# Sheet1.net
KiCad netlist of a schematic drawn in Altium Designer
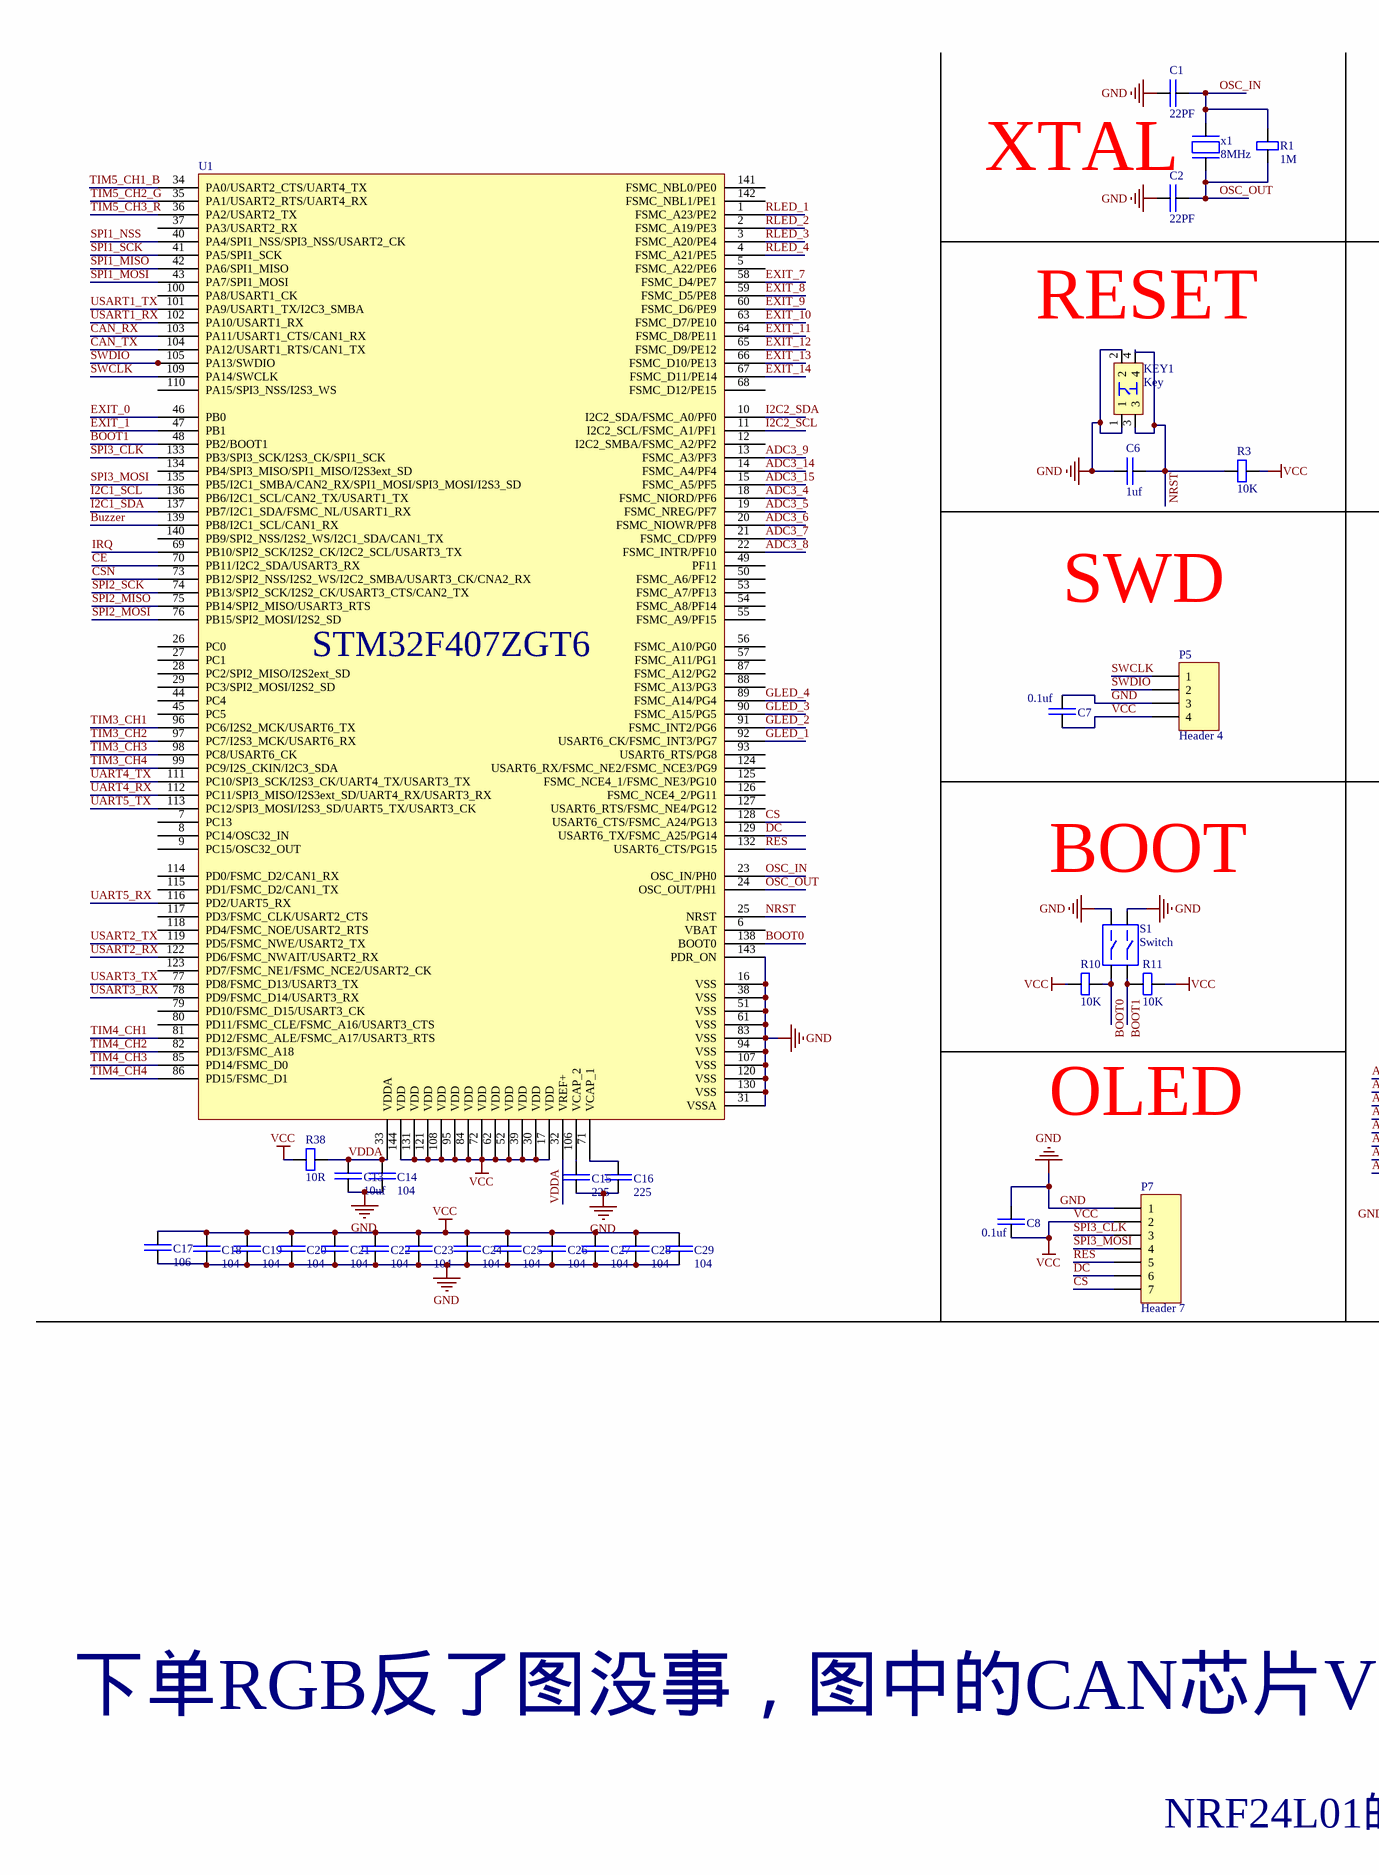
[diagram p0: Sheet1.SchDoc, left]
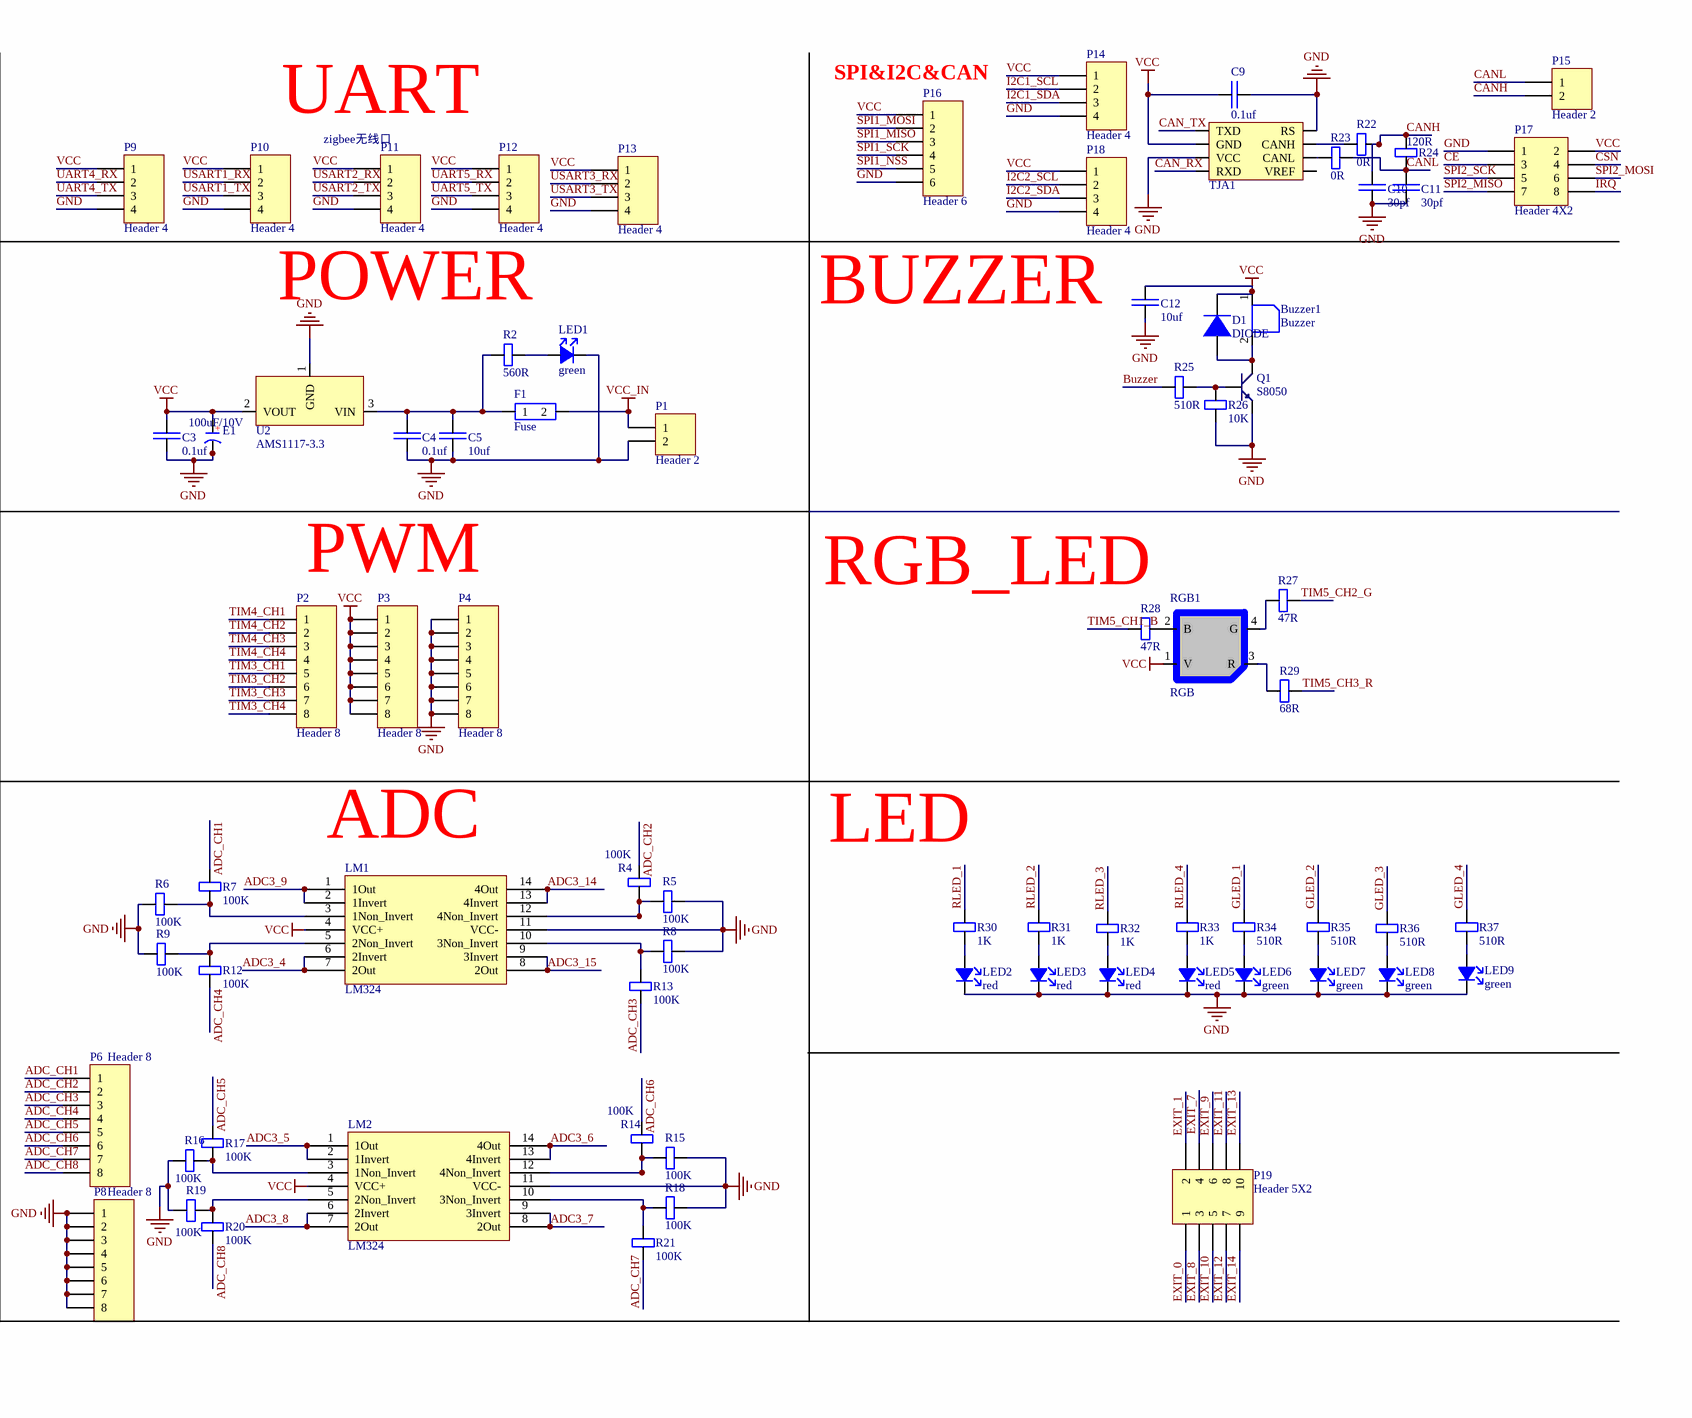
[diagram p1: Sheet1.SchDoc, right]

(export (version "E")
  (design (tool "Eeschema 10.0.6"))
  (components
    (comp (ref "Buzzer1") (value "Buzzer") (footprint "BUZZER") (libsource (lib "Schlib1") (part "Buzzer")))
    (comp (ref "C1") (value "22PF") (footprint "0402") (libsource (lib "Schlib1") (part "C")))
    (comp (ref "C2") (value "22PF") (footprint "0402") (libsource (lib "Schlib1") (part "C")))
    (comp (ref "C3") (value "0.1uf") (footprint "0402") (libsource (lib "Schlib1") (part "C")))
    (comp (ref "C4") (value "0.1uf") (footprint "0402") (libsource (lib "Schlib1") (part "C")))
    (comp (ref "C5") (value "10uf") (footprint "0402") (libsource (lib "Schlib1") (part "C")))
    (comp (ref "C6") (value "1uf") (footprint "0402") (libsource (lib "Schlib1") (part "C")))
    (comp (ref "C7") (value "0.1uf") (footprint "0402") (libsource (lib "Schlib1") (part "C")))
    (comp (ref "C8") (value "0.1uf") (footprint "0402") (libsource (lib "Schlib1") (part "C")))
    (comp (ref "C9") (value "0.1uf") (footprint "0402") (libsource (lib "Schlib1") (part "C")))
    (comp (ref "C10") (value "30pf") (footprint "0402") (libsource (lib "Schlib1") (part "C")))
    (comp (ref "C11") (value "30pf") (footprint "0402") (libsource (lib "Schlib1") (part "C")))
    (comp (ref "C12") (value "10uf") (footprint "0402") (libsource (lib "Schlib1") (part "C")))
    (comp (ref "C13") (value "10uf") (footprint "0402") (libsource (lib "Schlib1") (part "C")))
    (comp (ref "C14") (value "104") (footprint "0402") (libsource (lib "Schlib1") (part "C")))
    (comp (ref "C15") (value "225") (footprint "0402") (libsource (lib "Schlib1") (part "C")))
    (comp (ref "C16") (value "225") (footprint "0402") (libsource (lib "Schlib1") (part "C")))
    (comp (ref "C17") (value "106") (footprint "0402") (libsource (lib "Schlib1") (part "C")))
    (comp (ref "C18") (value "104") (footprint "0402") (libsource (lib "Schlib1") (part "C")))
    (comp (ref "C19") (value "104") (footprint "0402") (libsource (lib "Schlib1") (part "C")))
    (comp (ref "C20") (value "104") (footprint "0402") (libsource (lib "Schlib1") (part "C")))
    (comp (ref "C21") (value "104") (footprint "0402") (libsource (lib "Schlib1") (part "C")))
    (comp (ref "C22") (value "104") (footprint "0402") (libsource (lib "Schlib1") (part "C")))
    (comp (ref "C23") (value "104") (footprint "0402") (libsource (lib "Schlib1") (part "C")))
    (comp (ref "C24") (value "104") (footprint "0402") (libsource (lib "Schlib1") (part "C")))
    (comp (ref "C25") (value "104") (footprint "0402") (libsource (lib "Schlib1") (part "C")))
    (comp (ref "C26") (value "104") (footprint "0402") (libsource (lib "Schlib1") (part "C")))
    (comp (ref "C27") (value "104") (footprint "0402") (libsource (lib "Schlib1") (part "C")))
    (comp (ref "C28") (value "104") (footprint "0402") (libsource (lib "Schlib1") (part "C")))
    (comp (ref "C29") (value "104") (footprint "0402") (libsource (lib "Schlib1") (part "C")))
    (comp (ref "D1") (value "DIODE") (footprint "DIODE") (libsource (lib "Schlib1") (part "DIODE")))
    (comp (ref "E1")
      (value "100uF/10V")
      (footprint "3528")
      (description "钽电容")
      (fields (field (name "版权归属") "源创客"))
      (libsource (lib "电阻-电容-电感") (part "C-CM"))
    )
    (comp (ref "F1") (value "Fuse") (footprint "0805") (libsource (lib "Schlib1") (part "Fuse")))
    (comp (ref "KEY1") (value "Key") (footprint "6*6*5轻触开关") (libsource (lib "Schlib1") (part "Key")))
    (comp (ref "LED1") (value "green") (footprint "0603") (libsource (lib "Schlib1") (part "LED")))
    (comp (ref "LED2") (value "red") (footprint "0603") (libsource (lib "Schlib1") (part "LED")))
    (comp (ref "LED3") (value "red") (footprint "0603") (libsource (lib "Schlib1") (part "LED")))
    (comp (ref "LED4") (value "red") (footprint "0603") (libsource (lib "Schlib1") (part "LED")))
    (comp (ref "LED5") (value "red") (footprint "0603") (libsource (lib "Schlib1") (part "LED")))
    (comp (ref "LED6") (value "green") (footprint "0603") (libsource (lib "Schlib1") (part "LED")))
    (comp (ref "LED7") (value "green") (footprint "0603") (libsource (lib "Schlib1") (part "LED")))
    (comp (ref "LED8") (value "green") (footprint "0603") (libsource (lib "Schlib1") (part "LED")))
    (comp (ref "LED9") (value "green") (footprint "0603") (libsource (lib "Schlib1") (part "LED")))
    (comp (ref "LM1") (value "LM324") (footprint "LM324") (libsource (lib "Schlib1") (part "LM324")))
    (comp (ref "LM2") (value "LM324") (footprint "LM324") (libsource (lib "Schlib1") (part "LM324")))
    (comp (ref "P1")
      (value "Header 2")
      (footprint "XT30-PW-M")
      (description "Header, 2-Pin")
      (fields (field (name "PUBLISHER") "Altium Limited"))
      (libsource (lib "Miscellaneous Connectors") (part "Header 2"))
    )
    (comp (ref "P2")
      (value "Header 8")
      (footprint "HDR1X8")
      (description "Header, 8-Pin")
      (fields (field (name "PUBLISHER") "Altium Limited"))
      (libsource (lib "Miscellaneous Connectors") (part "Header 8"))
    )
    (comp (ref "P3")
      (value "Header 8")
      (footprint "HDR1X8")
      (description "Header, 8-Pin")
      (fields (field (name "PUBLISHER") "Altium Limited"))
      (libsource (lib "Miscellaneous Connectors") (part "Header 8"))
    )
    (comp (ref "P4")
      (value "Header 8")
      (footprint "HDR1X8")
      (description "Header, 8-Pin")
      (fields (field (name "PUBLISHER") "Altium Limited"))
      (libsource (lib "Miscellaneous Connectors") (part "Header 8"))
    )
    (comp (ref "P5")
      (value "Header 4")
      (footprint "GH1.25_4P")
      (description "Header, 4-Pin")
      (fields (field (name "PUBLISHER") "Altium Limited"))
      (libsource (lib "Miscellaneous Connectors") (part "Header 4"))
    )
    (comp (ref "P6")
      (value "Header 8")
      (footprint "HDR1X8")
      (description "Header, 8-Pin")
      (fields (field (name "PUBLISHER") "Altium Limited"))
      (libsource (lib "Miscellaneous Connectors") (part "Header 8"))
    )
    (comp (ref "P7")
      (value "Header 7")
      (footprint "HDR1X7")
      (description "Header, 7-Pin")
      (fields (field (name "PUBLISHER") "Altium Limited"))
      (libsource (lib "Miscellaneous Connectors") (part "Header 7"))
    )
    (comp (ref "P8")
      (value "Header 8")
      (footprint "HDR1X8")
      (description "Header, 8-Pin")
      (fields (field (name "PUBLISHER") "Altium Limited"))
      (libsource (lib "Miscellaneous Connectors") (part "Header 8"))
    )
    (comp (ref "P9")
      (value "Header 4")
      (footprint "GH1.25_4P")
      (description "Header, 4-Pin")
      (fields (field (name "PUBLISHER") "Altium Limited"))
      (libsource (lib "Miscellaneous Connectors") (part "Header 4"))
    )
    (comp (ref "P10")
      (value "Header 4")
      (footprint "GH1.25_4P")
      (description "Header, 4-Pin")
      (fields (field (name "PUBLISHER") "Altium Limited"))
      (libsource (lib "Miscellaneous Connectors") (part "Header 4"))
    )
    (comp (ref "P11")
      (value "Header 4")
      (footprint "GH1.25_4P")
      (description "Header, 4-Pin")
      (fields (field (name "PUBLISHER") "Altium Limited"))
      (libsource (lib "Miscellaneous Connectors") (part "Header 4"))
    )
    (comp (ref "P12")
      (value "Header 4")
      (footprint "GH1.25_4P")
      (description "Header, 4-Pin")
      (fields (field (name "PUBLISHER") "Altium Limited"))
      (libsource (lib "Miscellaneous Connectors") (part "Header 4"))
    )
    (comp (ref "P13")
      (value "Header 4")
      (footprint "GH1.25_4P")
      (description "Header, 4-Pin")
      (fields (field (name "PUBLISHER") "Altium Limited"))
      (libsource (lib "Miscellaneous Connectors") (part "Header 4"))
    )
    (comp (ref "P14")
      (value "Header 4")
      (footprint "GH1.25_4P")
      (description "Header, 4-Pin")
      (fields (field (name "PUBLISHER") "Altium Limited"))
      (libsource (lib "Miscellaneous Connectors") (part "Header 4"))
    )
    (comp (ref "P15")
      (value "Header 2")
      (footprint "GH1.25_2P")
      (description "Header, 2-Pin")
      (fields (field (name "PUBLISHER") "Altium Limited"))
      (libsource (lib "Miscellaneous Connectors") (part "Header 2"))
    )
    (comp (ref "P16")
      (value "Header 6")
      (footprint "HDR1X6")
      (description "Header, 6-Pin")
      (fields (field (name "PUBLISHER") "Altium Limited"))
      (libsource (lib "Miscellaneous Connectors") (part "Header 6"))
    )
    (comp (ref "P17")
      (value "Header 4X2")
      (footprint "HDR2X4")
      (description "Header, 4-Pin, Dual row")
      (fields (field (name "PUBLISHER") "Altium Limited"))
      (libsource (lib "Miscellaneous Connectors") (part "Header 4X2"))
    )
    (comp (ref "P18")
      (value "Header 4")
      (footprint "GH1.25_4P")
      (description "Header, 4-Pin")
      (fields (field (name "PUBLISHER") "Altium Limited"))
      (libsource (lib "Miscellaneous Connectors") (part "Header 4"))
    )
    (comp (ref "P19")
      (value "Header 5X2")
      (footprint "HDR2X5")
      (description "Header, 5-Pin, Dual row")
      (fields (field (name "PUBLISHER") "Altium Limited"))
      (libsource (lib "Miscellaneous Connectors") (part "Header 5X2"))
    )
    (comp (ref "Q1")
      (value "S8050")
      (footprint "SOT-23R")
      (description "8050/BCW846/BCW847")
      (libsource (lib "REMOTOR V1.6") (part "NPN"))
    )
    (comp (ref "R1") (value "1M") (footprint "0402") (libsource (lib "Schlib1") (part "R")))
    (comp (ref "R2") (value "560R") (footprint "0402") (libsource (lib "Schlib1") (part "R")))
    (comp (ref "R3") (value "10K") (footprint "0402") (libsource (lib "Schlib1") (part "R")))
    (comp (ref "R4") (value "100K") (footprint "0402") (libsource (lib "Schlib1") (part "R")))
    (comp (ref "R5") (value "100K") (footprint "0402") (libsource (lib "Schlib1") (part "R")))
    (comp (ref "R6") (value "100K") (footprint "0402") (libsource (lib "Schlib1") (part "R")))
    (comp (ref "R7") (value "100K") (footprint "0402") (libsource (lib "Schlib1") (part "R")))
    (comp (ref "R8") (value "100K") (footprint "0402") (libsource (lib "Schlib1") (part "R")))
    (comp (ref "R9") (value "100K") (footprint "0402") (libsource (lib "Schlib1") (part "R")))
    (comp (ref "R10") (value "10K") (footprint "0402") (libsource (lib "Schlib1") (part "R")))
    (comp (ref "R11") (value "10K") (footprint "0402") (libsource (lib "Schlib1") (part "R")))
    (comp (ref "R12") (value "100K") (footprint "0402") (libsource (lib "Schlib1") (part "R")))
    (comp (ref "R13") (value "100K") (footprint "0402") (libsource (lib "Schlib1") (part "R")))
    (comp (ref "R14") (value "100K") (footprint "0402") (libsource (lib "Schlib1") (part "R")))
    (comp (ref "R15") (value "100K") (footprint "0402") (libsource (lib "Schlib1") (part "R")))
    (comp (ref "R16") (value "100K") (footprint "0402") (libsource (lib "Schlib1") (part "R")))
    (comp (ref "R17") (value "100K") (footprint "0402") (libsource (lib "Schlib1") (part "R")))
    (comp (ref "R18") (value "100K") (footprint "0402") (libsource (lib "Schlib1") (part "R")))
    (comp (ref "R19") (value "100K") (footprint "0402") (libsource (lib "Schlib1") (part "R")))
    (comp (ref "R20") (value "100K") (footprint "0402") (libsource (lib "Schlib1") (part "R")))
    (comp (ref "R21") (value "100K") (footprint "0402") (libsource (lib "Schlib1") (part "R")))
    (comp (ref "R22") (value "0R") (footprint "0402") (libsource (lib "Schlib1") (part "R")))
    (comp (ref "R23") (value "0R") (footprint "0402") (libsource (lib "Schlib1") (part "R")))
    (comp (ref "R24") (value "120R") (footprint "0402") (libsource (lib "Schlib1") (part "R")))
    (comp (ref "R25") (value "510R") (footprint "0402") (libsource (lib "Schlib1") (part "R")))
    (comp (ref "R26") (value "10K") (footprint "0402") (libsource (lib "Schlib1") (part "R")))
    (comp (ref "R27") (value "47R") (footprint "0402") (libsource (lib "Schlib1") (part "R")))
    (comp (ref "R28") (value "47R") (footprint "0402") (libsource (lib "Schlib1") (part "R")))
    (comp (ref "R29") (value "68R") (footprint "0402") (libsource (lib "Schlib1") (part "R")))
    (comp (ref "R30") (value "1K") (footprint "0402") (libsource (lib "Schlib1") (part "R")))
    (comp (ref "R31") (value "1K") (footprint "0402") (libsource (lib "Schlib1") (part "R")))
    (comp (ref "R32") (value "1K") (footprint "0402") (libsource (lib "Schlib1") (part "R")))
    (comp (ref "R33") (value "1K") (footprint "0402") (libsource (lib "Schlib1") (part "R")))
    (comp (ref "R34") (value "510R") (footprint "0402") (libsource (lib "Schlib1") (part "R")))
    (comp (ref "R35") (value "510R") (footprint "0402") (libsource (lib "Schlib1") (part "R")))
    (comp (ref "R36") (value "510R") (footprint "0402") (libsource (lib "Schlib1") (part "R")))
    (comp (ref "R37") (value "510R") (footprint "0402") (libsource (lib "Schlib1") (part "R")))
    (comp (ref "R38") (value "10R") (footprint "0402") (libsource (lib "Schlib1") (part "R")))
    (comp (ref "RGB1") (value "RGB") (footprint "RGB_LED") (libsource (lib "Schlib1") (part "RGB")))
    (comp (ref "S1") (value "Switch") (footprint "SWITCH_2P") (libsource (lib "Schlib1") (part "Switch")))
    (comp (ref "TJA1") (value "TJA1050") (footprint "TJA1050") (libsource (lib "Schlib1") (part "TJA1050")))
    (comp (ref "U1")
      (value "STM32F407ZGT6")
      (footprint "STM32F103ZETx")
      (libsource (lib "Schlib1") (part "STM32F407ZGT6"))
    )
    (comp (ref "U2")
      (value "AMS1117-3.3")
      (footprint "ASM1117")
      (libsource (lib "Schlib1") (part "AMS1117-3.3"))
    )
    (comp (ref "x1") (value "8MHz") (footprint "8M晶振") (libsource (lib "Schlib1") (part "XTAL_8MHz")))
  )
  (nets
    (net (code "1") (name "/ADC3_4") (class "Default")
      (node (ref "LM1") (pin "6") (pinfunction "2Invert_6") (pintype "passive"))
      (node (ref "LM1") (pin "7") (pinfunction "2Out_7") (pintype "passive"))
      (node (ref "U1") (pin "18") (pinfunction "FSMC_NIORD/PF6_18") (pintype "passive"))
    )
    (net (code "2") (name "/ADC3_5") (class "Default")
      (node (ref "LM2") (pin "1") (pinfunction "1Out_1") (pintype "passive"))
      (node (ref "LM2") (pin "2") (pinfunction "1Invert_2") (pintype "passive"))
      (node (ref "U1") (pin "19") (pinfunction "FSMC_NREG/PF7_19") (pintype "passive"))
    )
    (net (code "3") (name "/ADC3_6") (class "Default")
      (node (ref "LM2") (pin "13") (pinfunction "4Invert_13") (pintype "passive"))
      (node (ref "LM2") (pin "14") (pinfunction "4Out_14") (pintype "passive"))
      (node (ref "U1") (pin "20") (pinfunction "FSMC_NIOWR/PF8_20") (pintype "passive"))
    )
    (net (code "4") (name "/ADC3_7") (class "Default")
      (node (ref "LM2") (pin "8") (pinfunction "2Out_8") (pintype "passive"))
      (node (ref "LM2") (pin "9") (pinfunction "3Invert_9") (pintype "passive"))
      (node (ref "U1") (pin "21") (pinfunction "FSMC_CD/PF9_21") (pintype "passive"))
    )
    (net (code "5") (name "/ADC3_8") (class "Default")
      (node (ref "LM2") (pin "6") (pinfunction "2Invert_6") (pintype "passive"))
      (node (ref "LM2") (pin "7") (pinfunction "2Out_7") (pintype "passive"))
      (node (ref "U1") (pin "22") (pinfunction "FSMC_INTR/PF10_22") (pintype "passive"))
    )
    (net (code "6") (name "/ADC3_9") (class "Default")
      (node (ref "LM1") (pin "1") (pinfunction "1Out_1") (pintype "passive"))
      (node (ref "LM1") (pin "2") (pinfunction "1Invert_2") (pintype "passive"))
      (node (ref "U1") (pin "13") (pinfunction "FSMC_A3/PF3_13") (pintype "passive"))
    )
    (net (code "7") (name "/ADC3_14") (class "Default")
      (node (ref "LM1") (pin "13") (pinfunction "4Invert_13") (pintype "passive"))
      (node (ref "LM1") (pin "14") (pinfunction "4Out_14") (pintype "passive"))
      (node (ref "U1") (pin "14") (pinfunction "FSMC_A4/PF4_14") (pintype "passive"))
    )
    (net (code "8") (name "/ADC3_15") (class "Default")
      (node (ref "LM1") (pin "8") (pinfunction "2Out_8") (pintype "passive"))
      (node (ref "LM1") (pin "9") (pinfunction "3Invert_9") (pintype "passive"))
      (node (ref "U1") (pin "15") (pinfunction "FSMC_A5/PF5_15") (pintype "passive"))
    )
    (net (code "9") (name "/ADC_CH1") (class "Default")
      (node (ref "P6") (pin "1") (pinfunction "1_1") (pintype "passive"))
      (node (ref "R7") (pin "2") (pinfunction "2_2") (pintype "passive"))
    )
    (net (code "10") (name "/ADC_CH2") (class "Default")
      (node (ref "P6") (pin "2") (pinfunction "2_2") (pintype "passive"))
      (node (ref "R4") (pin "1") (pinfunction "1_1") (pintype "passive"))
    )
    (net (code "11") (name "/ADC_CH3") (class "Default")
      (node (ref "P6") (pin "3") (pinfunction "3_3") (pintype "passive"))
      (node (ref "R13") (pin "2") (pinfunction "2_2") (pintype "passive"))
    )
    (net (code "12") (name "/ADC_CH4") (class "Default")
      (node (ref "P6") (pin "4") (pinfunction "4_4") (pintype "passive"))
      (node (ref "R12") (pin "2") (pinfunction "2_2") (pintype "passive"))
    )
    (net (code "13") (name "/ADC_CH5") (class "Default")
      (node (ref "P6") (pin "5") (pinfunction "5_5") (pintype "passive"))
      (node (ref "R17") (pin "2") (pinfunction "2_2") (pintype "passive"))
    )
    (net (code "14") (name "/ADC_CH6") (class "Default")
      (node (ref "P6") (pin "6") (pinfunction "6_6") (pintype "passive"))
      (node (ref "R14") (pin "1") (pinfunction "1_1") (pintype "passive"))
    )
    (net (code "15") (name "/ADC_CH7") (class "Default")
      (node (ref "P6") (pin "7") (pinfunction "7_7") (pintype "passive"))
      (node (ref "R21") (pin "2") (pinfunction "2_2") (pintype "passive"))
    )
    (net (code "16") (name "/ADC_CH8") (class "Default")
      (node (ref "P6") (pin "8") (pinfunction "8_8") (pintype "passive"))
      (node (ref "R20") (pin "2") (pinfunction "2_2") (pintype "passive"))
    )
    (net (code "17") (name "/BOOT0") (class "Default")
      (node (ref "R10") (pin "1") (pinfunction "1_1") (pintype "passive"))
      (node (ref "S1") (pin "2") (pinfunction "156_2") (pintype "passive"))
      (node (ref "U1") (pin "138") (pinfunction "BOOT0_138") (pintype "passive"))
    )
    (net (code "18") (name "/BOOT1") (class "Default")
      (node (ref "R11") (pin "2") (pinfunction "2_2") (pintype "passive"))
      (node (ref "S1") (pin "4") (pinfunction "157_4") (pintype "passive"))
      (node (ref "U1") (pin "48") (pinfunction "PB2/BOOT1_48") (pintype "passive"))
    )
    (net (code "19") (name "/Buzzer") (class "Default")
      (node (ref "R25") (pin "1") (pinfunction "1_1") (pintype "passive"))
      (node (ref "U1") (pin "139") (pinfunction "PB8/I2C1_SCL/CAN1_RX_139") (pintype "passive"))
    )
    (net (code "20") (name "/CANH") (class "Default")
      (node (ref "C10") (pin "2") (pinfunction "2_2") (pintype "passive"))
      (node (ref "P15") (pin "2") (pinfunction "2_2") (pintype "passive"))
      (node (ref "R22") (pin "2") (pinfunction "2_2") (pintype "passive"))
      (node (ref "R24") (pin "2") (pinfunction "2_2") (pintype "passive"))
    )
    (net (code "21") (name "/CANL") (class "Default")
      (node (ref "C11") (pin "2") (pinfunction "2_2") (pintype "passive"))
      (node (ref "P15") (pin "1") (pinfunction "1_1") (pintype "passive"))
      (node (ref "R23") (pin "2") (pinfunction "2_2") (pintype "passive"))
      (node (ref "R24") (pin "1") (pinfunction "1_1") (pintype "passive"))
    )
    (net (code "22") (name "/CAN_RX") (class "Default")
      (node (ref "TJA1") (pin "4") (pinfunction "RXD_4") (pintype "passive"))
      (node (ref "U1") (pin "103") (pinfunction "PA11/USART1_CTS/CAN1_RX_103") (pintype "passive"))
    )
    (net (code "23") (name "/CAN_TX") (class "Default")
      (node (ref "TJA1") (pin "1") (pinfunction "TXD_1") (pintype "passive"))
      (node (ref "U1") (pin "104") (pinfunction "PA12/USART1_RTS/CAN1_TX_104") (pintype "passive"))
    )
    (net (code "24") (name "/CE") (class "Default")
      (node (ref "P17") (pin "3") (pinfunction "3_3") (pintype "passive"))
      (node (ref "U1") (pin "70") (pinfunction "PB11/I2C2_SDA/USART3_RX_70") (pintype "passive"))
    )
    (net (code "25") (name "/CS") (class "Default")
      (node (ref "P7") (pin "7") (pinfunction "7_7") (pintype "passive"))
      (node (ref "U1") (pin "128") (pinfunction "USART6_CTS/FSMC_A24/PG13_128") (pintype "passive"))
    )
    (net (code "26") (name "/CSN") (class "Default")
      (node (ref "P17") (pin "4") (pinfunction "4_4") (pintype "passive"))
      (node (ref "U1") (pin "73") (pinfunction "PB12/SPI2_NSS/I2S2_WS/I2C2_SMBA/USART3_CK/CNA2_RX_73") (pintype "passive"))
    )
    (net (code "27") (name "/DC") (class "Default")
      (node (ref "P7") (pin "6") (pinfunction "6_6") (pintype "passive"))
      (node (ref "U1") (pin "129") (pinfunction "USART6_TX/FSMC_A25/PG14_129") (pintype "passive"))
    )
    (net (code "28") (name "/EXIT_0") (class "Default")
      (node (ref "P19") (pin "1") (pinfunction "1_1") (pintype "passive"))
      (node (ref "U1") (pin "46") (pinfunction "PB0_46") (pintype "passive"))
    )
    (net (code "29") (name "/EXIT_1") (class "Default")
      (node (ref "P19") (pin "2") (pinfunction "2_2") (pintype "passive"))
      (node (ref "U1") (pin "47") (pinfunction "PB1_47") (pintype "passive"))
    )
    (net (code "30") (name "/EXIT_7") (class "Default")
      (node (ref "P19") (pin "4") (pinfunction "4_4") (pintype "passive"))
      (node (ref "U1") (pin "58") (pinfunction "FSMC_D4/PE7_58") (pintype "passive"))
    )
    (net (code "31") (name "/EXIT_8") (class "Default")
      (node (ref "P19") (pin "3") (pinfunction "3_3") (pintype "passive"))
      (node (ref "U1") (pin "59") (pinfunction "FSMC_D5/PE8_59") (pintype "passive"))
    )
    (net (code "32") (name "/EXIT_9") (class "Default")
      (node (ref "P19") (pin "6") (pinfunction "6_6") (pintype "passive"))
      (node (ref "U1") (pin "60") (pinfunction "FSMC_D6/PE9_60") (pintype "passive"))
    )
    (net (code "33") (name "/EXIT_10") (class "Default")
      (node (ref "P19") (pin "5") (pinfunction "5_5") (pintype "passive"))
      (node (ref "U1") (pin "63") (pinfunction "FSMC_D7/PE10_63") (pintype "passive"))
    )
    (net (code "34") (name "/EXIT_11") (class "Default")
      (node (ref "P19") (pin "8") (pinfunction "8_8") (pintype "passive"))
      (node (ref "U1") (pin "64") (pinfunction "FSMC_D8/PE11_64") (pintype "passive"))
    )
    (net (code "35") (name "/EXIT_12") (class "Default")
      (node (ref "P19") (pin "7") (pinfunction "7_7") (pintype "passive"))
      (node (ref "U1") (pin "65") (pinfunction "FSMC_D9/PE12_65") (pintype "passive"))
    )
    (net (code "36") (name "/EXIT_13") (class "Default")
      (node (ref "P19") (pin "10") (pinfunction "10_10") (pintype "passive"))
      (node (ref "U1") (pin "66") (pinfunction "FSMC_D10/PE13_66") (pintype "passive"))
    )
    (net (code "37") (name "/EXIT_14") (class "Default")
      (node (ref "P19") (pin "9") (pinfunction "9_9") (pintype "passive"))
      (node (ref "U1") (pin "67") (pinfunction "FSMC_D11/PE14_67") (pintype "passive"))
    )
    (net (code "38") (name "/GLED_1") (class "Default")
      (node (ref "R34") (pin "2") (pinfunction "2_2") (pintype "passive"))
      (node (ref "U1") (pin "92") (pinfunction "USART6_CK/FSMC_INT3/PG7_92") (pintype "passive"))
    )
    (net (code "39") (name "/GLED_2") (class "Default")
      (node (ref "R35") (pin "2") (pinfunction "2_2") (pintype "passive"))
      (node (ref "U1") (pin "91") (pinfunction "FSMC_INT2/PG6_91") (pintype "passive"))
    )
    (net (code "40") (name "/GLED_3") (class "Default")
      (node (ref "R36") (pin "2") (pinfunction "2_2") (pintype "passive"))
      (node (ref "U1") (pin "90") (pinfunction "FSMC_A15/PG5_90") (pintype "passive"))
    )
    (net (code "41") (name "/GLED_4") (class "Default")
      (node (ref "R37") (pin "2") (pinfunction "2_2") (pintype "passive"))
      (node (ref "U1") (pin "89") (pinfunction "FSMC_A14/PG4_89") (pintype "passive"))
    )
    (net (code "42") (name "/I2C1_SCL") (class "Default")
      (node (ref "P14") (pin "2") (pinfunction "2_2") (pintype "passive"))
      (node (ref "U1") (pin "136") (pinfunction "PB6/I2C1_SCL/CAN2_TX/USART1_TX_136") (pintype "passive"))
    )
    (net (code "43") (name "/I2C1_SDA") (class "Default")
      (node (ref "P14") (pin "3") (pinfunction "3_3") (pintype "passive"))
      (node (ref "U1") (pin "137") (pinfunction "PB7/I2C1_SDA/FSMC_NL/USART1_RX_137") (pintype "passive"))
    )
    (net (code "44") (name "/I2C2_SCL") (class "Default")
      (node (ref "P18") (pin "2") (pinfunction "2_2") (pintype "passive"))
      (node (ref "U1") (pin "11") (pinfunction "I2C2_SCL/FSMC_A1/PF1_11") (pintype "passive"))
    )
    (net (code "45") (name "/I2C2_SDA") (class "Default")
      (node (ref "P18") (pin "3") (pinfunction "3_3") (pintype "passive"))
      (node (ref "U1") (pin "10") (pinfunction "I2C2_SDA/FSMC_A0/PF0_10") (pintype "passive"))
    )
    (net (code "46") (name "/IRQ") (class "Default")
      (node (ref "P17") (pin "8") (pinfunction "8_8") (pintype "passive"))
      (node (ref "U1") (pin "69") (pinfunction "PB10/SPI2_SCK/I2S2_CK/I2C2_SCL/USART3_TX_69") (pintype "passive"))
    )
    (net (code "47") (name "/NRST") (class "Default")
      (node (ref "C6") (pin "1") (pinfunction "1_1") (pintype "passive"))
      (node (ref "KEY1") (pin "3") (pinfunction "3_3") (pintype "passive"))
      (node (ref "KEY1") (pin "4") (pinfunction "4_4") (pintype "passive"))
      (node (ref "R3") (pin "1") (pinfunction "1_1") (pintype "passive"))
      (node (ref "U1") (pin "25") (pinfunction "NRST_25") (pintype "passive"))
    )
    (net (code "48") (name "/OSC_IN") (class "Default")
      (node (ref "C1") (pin "1") (pinfunction "1_1") (pintype "passive"))
      (node (ref "R1") (pin "2") (pinfunction "2_2") (pintype "passive"))
      (node (ref "U1") (pin "23") (pinfunction "OSC_IN/PH0_23") (pintype "passive"))
      (node (ref "x1") (pin "1") (pinfunction "1_1") (pintype "passive"))
    )
    (net (code "49") (name "/OSC_OUT") (class "Default")
      (node (ref "C2") (pin "1") (pinfunction "1_1") (pintype "passive"))
      (node (ref "R1") (pin "1") (pinfunction "1_1") (pintype "passive"))
      (node (ref "U1") (pin "24") (pinfunction "OSC_OUT/PH1_24") (pintype "passive"))
      (node (ref "x1") (pin "2") (pinfunction "2_2") (pintype "passive"))
    )
    (net (code "50") (name "/RES") (class "Default")
      (node (ref "P7") (pin "5") (pinfunction "5_5") (pintype "passive"))
      (node (ref "U1") (pin "132") (pinfunction "USART6_CTS/PG15_132") (pintype "passive"))
    )
    (net (code "51") (name "/RLED_1") (class "Default")
      (node (ref "R30") (pin "2") (pinfunction "2_2") (pintype "passive"))
      (node (ref "U1") (pin "1") (pinfunction "FSMC_A23/PE2_1") (pintype "passive"))
    )
    (net (code "52") (name "/RLED_2") (class "Default")
      (node (ref "R31") (pin "2") (pinfunction "2_2") (pintype "passive"))
      (node (ref "U1") (pin "2") (pinfunction "FSMC_A19/PE3_2") (pintype "passive"))
    )
    (net (code "53") (name "/RLED_3") (class "Default")
      (node (ref "R32") (pin "2") (pinfunction "2_2") (pintype "passive"))
      (node (ref "U1") (pin "3") (pinfunction "FSMC_A20/PE4_3") (pintype "passive"))
    )
    (net (code "54") (name "/RLED_4") (class "Default")
      (node (ref "R33") (pin "2") (pinfunction "2_2") (pintype "passive"))
      (node (ref "U1") (pin "4") (pinfunction "FSMC_A21/PE5_4") (pintype "passive"))
    )
    (net (code "55") (name "/SPI1_MISO") (class "Default")
      (node (ref "P16") (pin "3") (pinfunction "3_3") (pintype "passive"))
      (node (ref "U1") (pin "42") (pinfunction "PA6/SPI1_MISO_42") (pintype "passive"))
    )
    (net (code "56") (name "/SPI1_MOSI") (class "Default")
      (node (ref "P16") (pin "2") (pinfunction "2_2") (pintype "passive"))
      (node (ref "U1") (pin "43") (pinfunction "PA7/SPI1_MOSI_43") (pintype "passive"))
    )
    (net (code "57") (name "/SPI1_NSS") (class "Default")
      (node (ref "P16") (pin "5") (pinfunction "5_5") (pintype "passive"))
      (node (ref "U1") (pin "40") (pinfunction "PA4/SPI1_NSS/SPI3_NSS/USART2_CK_40") (pintype "passive"))
    )
    (net (code "58") (name "/SPI1_SCK") (class "Default")
      (node (ref "P16") (pin "4") (pinfunction "4_4") (pintype "passive"))
      (node (ref "U1") (pin "41") (pinfunction "PA5/SPI1_SCK_41") (pintype "passive"))
    )
    (net (code "59") (name "/SPI2_MISO") (class "Default")
      (node (ref "P17") (pin "7") (pinfunction "7_7") (pintype "passive"))
      (node (ref "U1") (pin "75") (pinfunction "PB14/SPI2_MISO/USART3_RTS_75") (pintype "passive"))
    )
    (net (code "60") (name "/SPI2_MOSI") (class "Default")
      (node (ref "P17") (pin "6") (pinfunction "6_6") (pintype "passive"))
      (node (ref "U1") (pin "76") (pinfunction "PB15/SPI2_MOSI/I2S2_SD_76") (pintype "passive"))
    )
    (net (code "61") (name "/SPI2_SCK") (class "Default")
      (node (ref "P17") (pin "5") (pinfunction "5_5") (pintype "passive"))
      (node (ref "U1") (pin "74") (pinfunction "PB13/SPI2_SCK/I2S2_CK/USART3_CTS/CAN2_TX_74") (pintype "passive"))
    )
    (net (code "62") (name "/SPI3_CLK") (class "Default")
      (node (ref "P7") (pin "3") (pinfunction "3_3") (pintype "passive"))
      (node (ref "U1") (pin "133") (pinfunction "PB3/SPI3_SCK/I2S3_CK/SPI1_SCK_133") (pintype "passive"))
    )
    (net (code "63") (name "/SPI3_MOSI") (class "Default")
      (node (ref "P7") (pin "4") (pinfunction "4_4") (pintype "passive"))
      (node (ref "U1") (pin "135") (pinfunction "PB5/I2C1_SMBA/CAN2_RX/SPI1_MOSI/SPI3_MOSI/I2S3_SD_135") (pintype "passive"))
    )
    (net (code "64") (name "/SWCLK") (class "Default")
      (node (ref "P5") (pin "1") (pinfunction "1_1") (pintype "passive"))
      (node (ref "U1") (pin "109") (pinfunction "PA14/SWCLK_109") (pintype "passive"))
    )
    (net (code "65") (name "/SWDIO") (class "Default")
      (node (ref "P5") (pin "2") (pinfunction "2_2") (pintype "passive"))
      (node (ref "U1") (pin "105") (pinfunction "PA13/SWDIO_105") (pintype "passive"))
    )
    (net (code "66") (name "/TIM3_CH1") (class "Default")
      (node (ref "P2") (pin "5") (pinfunction "5_5") (pintype "passive"))
      (node (ref "U1") (pin "96") (pinfunction "PC6/I2S2_MCK/USART6_TX_96") (pintype "passive"))
    )
    (net (code "67") (name "/TIM3_CH2") (class "Default")
      (node (ref "P2") (pin "6") (pinfunction "6_6") (pintype "passive"))
      (node (ref "U1") (pin "97") (pinfunction "PC7/I2S3_MCK/USART6_RX_97") (pintype "passive"))
    )
    (net (code "68") (name "/TIM3_CH3") (class "Default")
      (node (ref "P2") (pin "7") (pinfunction "7_7") (pintype "passive"))
      (node (ref "U1") (pin "98") (pinfunction "PC8/USART6_CK_98") (pintype "passive"))
    )
    (net (code "69") (name "/TIM3_CH4") (class "Default")
      (node (ref "P2") (pin "8") (pinfunction "8_8") (pintype "passive"))
      (node (ref "U1") (pin "99") (pinfunction "PC9/I2S_CKIN/I2C3_SDA_99") (pintype "passive"))
    )
    (net (code "70") (name "/TIM4_CH1") (class "Default")
      (node (ref "P2") (pin "1") (pinfunction "1_1") (pintype "passive"))
      (node (ref "U1") (pin "81") (pinfunction "PD12/FSMC_ALE/FSMC_A17/USART3_RTS_81") (pintype "passive"))
    )
    (net (code "71") (name "/TIM4_CH2") (class "Default")
      (node (ref "P2") (pin "2") (pinfunction "2_2") (pintype "passive"))
      (node (ref "U1") (pin "82") (pinfunction "PD13/FSMC_A18_82") (pintype "passive"))
    )
    (net (code "72") (name "/TIM4_CH3") (class "Default")
      (node (ref "P2") (pin "3") (pinfunction "3_3") (pintype "passive"))
      (node (ref "U1") (pin "85") (pinfunction "PD14/FSMC_D0_85") (pintype "passive"))
    )
    (net (code "73") (name "/TIM4_CH4") (class "Default")
      (node (ref "P2") (pin "4") (pinfunction "4_4") (pintype "passive"))
      (node (ref "U1") (pin "86") (pinfunction "PD15/FSMC_D1_86") (pintype "passive"))
    )
    (net (code "74") (name "/TIM5_CH1_B") (class "Default")
      (node (ref "R28") (pin "2") (pinfunction "2_2") (pintype "passive"))
      (node (ref "U1") (pin "34") (pinfunction "PA0/USART2_CTS/UART4_TX_34") (pintype "passive"))
    )
    (net (code "75") (name "/TIM5_CH2_G") (class "Default")
      (node (ref "R27") (pin "1") (pinfunction "1_1") (pintype "passive"))
      (node (ref "U1") (pin "35") (pinfunction "PA1/USART2_RTS/UART4_RX_35") (pintype "passive"))
    )
    (net (code "76") (name "/TIM5_CH3_R") (class "Default")
      (node (ref "R29") (pin "1") (pinfunction "1_1") (pintype "passive"))
      (node (ref "U1") (pin "36") (pinfunction "PA2/USART2_TX_36") (pintype "passive"))
    )
    (net (code "77") (name "/UART4_RX") (class "Default")
      (node (ref "P9") (pin "2") (pinfunction "2_2") (pintype "passive"))
      (node (ref "U1") (pin "112") (pinfunction "PC11/SPI3_MISO/I2S3ext_SD/UART4_RX/USART3_RX_112") (pintype "passive"))
    )
    (net (code "78") (name "/UART4_TX") (class "Default")
      (node (ref "P9") (pin "3") (pinfunction "3_3") (pintype "passive"))
      (node (ref "U1") (pin "111") (pinfunction "PC10/SPI3_SCK/I2S3_CK/UART4_TX/USART3_TX_111") (pintype "passive"))
    )
    (net (code "79") (name "/UART5_RX") (class "Default")
      (node (ref "P12") (pin "2") (pinfunction "2_2") (pintype "passive"))
      (node (ref "U1") (pin "116") (pinfunction "PD2/UART5_RX_116") (pintype "passive"))
    )
    (net (code "80") (name "/UART5_TX") (class "Default")
      (node (ref "P12") (pin "3") (pinfunction "3_3") (pintype "passive"))
      (node (ref "U1") (pin "113") (pinfunction "PC12/SPI3_MOSI/I2S3_SD/UART5_TX/USART3_CK_113") (pintype "passive"))
    )
    (net (code "81") (name "/USART1_RX") (class "Default")
      (node (ref "P10") (pin "2") (pinfunction "2_2") (pintype "passive"))
      (node (ref "U1") (pin "102") (pinfunction "PA10/USART1_RX_102") (pintype "passive"))
    )
    (net (code "82") (name "/USART1_TX") (class "Default")
      (node (ref "P10") (pin "3") (pinfunction "3_3") (pintype "passive"))
      (node (ref "U1") (pin "101") (pinfunction "PA9/USART1_TX/I2C3_SMBA_101") (pintype "passive"))
    )
    (net (code "83") (name "/USART2_RX") (class "Default")
      (node (ref "P11") (pin "2") (pinfunction "2_2") (pintype "passive"))
      (node (ref "U1") (pin "122") (pinfunction "PD6/FSMC_NWAIT/USART2_RX_122") (pintype "passive"))
    )
    (net (code "84") (name "/USART2_TX") (class "Default")
      (node (ref "P11") (pin "3") (pinfunction "3_3") (pintype "passive"))
      (node (ref "U1") (pin "119") (pinfunction "PD5/FSMC_NWE/USART2_TX_119") (pintype "passive"))
    )
    (net (code "85") (name "/USART3_RX") (class "Default")
      (node (ref "P13") (pin "2") (pinfunction "2_2") (pintype "passive"))
      (node (ref "U1") (pin "78") (pinfunction "PD9/FSMC_D14/USART3_RX_78") (pintype "passive"))
    )
    (net (code "86") (name "/USART3_TX") (class "Default")
      (node (ref "P13") (pin "3") (pinfunction "3_3") (pintype "passive"))
      (node (ref "U1") (pin "77") (pinfunction "PD8/FSMC_D13/USART3_TX_77") (pintype "passive"))
    )
    (net (code "87") (name "/VDDA") (class "Default")
      (node (ref "C13") (pin "2") (pinfunction "2_2") (pintype "passive"))
      (node (ref "C14") (pin "2") (pinfunction "2_2") (pintype "passive"))
      (node (ref "R38") (pin "2") (pinfunction "2_2") (pintype "passive"))
      (node (ref "U1") (pin "32") (pinfunction "VREF+_32") (pintype "passive"))
      (node (ref "U1") (pin "33") (pinfunction "VDDA_33") (pintype "passive"))
    )
    (net (code "88") (name "GND") (class "Default")
      (node (ref "C1") (pin "2") (pinfunction "2_2") (pintype "passive"))
      (node (ref "C10") (pin "1") (pinfunction "1_1") (pintype "passive"))
      (node (ref "C11") (pin "1") (pinfunction "1_1") (pintype "passive"))
      (node (ref "C12") (pin "1") (pinfunction "1_1") (pintype "passive"))
      (node (ref "C13") (pin "1") (pinfunction "1_1") (pintype "passive"))
      (node (ref "C14") (pin "1") (pinfunction "1_1") (pintype "passive"))
      (node (ref "C15") (pin "1") (pinfunction "1_1") (pintype "passive"))
      (node (ref "C16") (pin "1") (pinfunction "1_1") (pintype "passive"))
      (node (ref "C17") (pin "1") (pinfunction "1_1") (pintype "passive"))
      (node (ref "C18") (pin "1") (pinfunction "1_1") (pintype "passive"))
      (node (ref "C19") (pin "1") (pinfunction "1_1") (pintype "passive"))
      (node (ref "C2") (pin "2") (pinfunction "2_2") (pintype "passive"))
      (node (ref "C20") (pin "1") (pinfunction "1_1") (pintype "passive"))
      (node (ref "C21") (pin "1") (pinfunction "1_1") (pintype "passive"))
      (node (ref "C22") (pin "1") (pinfunction "1_1") (pintype "passive"))
      (node (ref "C23") (pin "1") (pinfunction "1_1") (pintype "passive"))
      (node (ref "C24") (pin "1") (pinfunction "1_1") (pintype "passive"))
      (node (ref "C25") (pin "1") (pinfunction "1_1") (pintype "passive"))
      (node (ref "C26") (pin "1") (pinfunction "1_1") (pintype "passive"))
      (node (ref "C27") (pin "1") (pinfunction "1_1") (pintype "passive"))
      (node (ref "C28") (pin "1") (pinfunction "1_1") (pintype "passive"))
      (node (ref "C29") (pin "1") (pinfunction "1_1") (pintype "passive"))
      (node (ref "C3") (pin "2") (pinfunction "2_2") (pintype "passive"))
      (node (ref "C4") (pin "2") (pinfunction "2_2") (pintype "passive"))
      (node (ref "C5") (pin "2") (pinfunction "2_2") (pintype "passive"))
      (node (ref "C6") (pin "2") (pinfunction "2_2") (pintype "passive"))
      (node (ref "C7") (pin "1") (pinfunction "1_1") (pintype "passive"))
      (node (ref "C8") (pin "1") (pinfunction "1_1") (pintype "passive"))
      (node (ref "C9") (pin "2") (pinfunction "2_2") (pintype "passive"))
      (node (ref "E1") (pin "2") (pinfunction "K_2") (pintype "passive"))
      (node (ref "KEY1") (pin "1") (pinfunction "1_1") (pintype "passive"))
      (node (ref "KEY1") (pin "2") (pinfunction "2_2") (pintype "passive"))
      (node (ref "LED1") (pin "2") (pinfunction "2_2") (pintype "passive"))
      (node (ref "LED2") (pin "2") (pinfunction "2_2") (pintype "passive"))
      (node (ref "LED3") (pin "2") (pinfunction "2_2") (pintype "passive"))
      (node (ref "LED4") (pin "2") (pinfunction "2_2") (pintype "passive"))
      (node (ref "LED5") (pin "2") (pinfunction "2_2") (pintype "passive"))
      (node (ref "LED6") (pin "2") (pinfunction "2_2") (pintype "passive"))
      (node (ref "LED7") (pin "2") (pinfunction "2_2") (pintype "passive"))
      (node (ref "LED8") (pin "2") (pinfunction "2_2") (pintype "passive"))
      (node (ref "LED9") (pin "2") (pinfunction "2_2") (pintype "passive"))
      (node (ref "LM1") (pin "11") (pinfunction "VCC-_11") (pintype "passive"))
      (node (ref "LM2") (pin "11") (pinfunction "VCC-_11") (pintype "passive"))
      (node (ref "P1") (pin "2") (pinfunction "2_2") (pintype "passive"))
      (node (ref "P10") (pin "4") (pinfunction "4_4") (pintype "passive"))
      (node (ref "P11") (pin "4") (pinfunction "4_4") (pintype "passive"))
      (node (ref "P12") (pin "4") (pinfunction "4_4") (pintype "passive"))
      (node (ref "P13") (pin "4") (pinfunction "4_4") (pintype "passive"))
      (node (ref "P14") (pin "4") (pinfunction "4_4") (pintype "passive"))
      (node (ref "P16") (pin "6") (pinfunction "6_6") (pintype "passive"))
      (node (ref "P17") (pin "1") (pinfunction "1_1") (pintype "passive"))
      (node (ref "P18") (pin "4") (pinfunction "4_4") (pintype "passive"))
      (node (ref "P4") (pin "1") (pinfunction "1_1") (pintype "passive"))
      (node (ref "P4") (pin "2") (pinfunction "2_2") (pintype "passive"))
      (node (ref "P4") (pin "3") (pinfunction "3_3") (pintype "passive"))
      (node (ref "P4") (pin "4") (pinfunction "4_4") (pintype "passive"))
      (node (ref "P4") (pin "5") (pinfunction "5_5") (pintype "passive"))
      (node (ref "P4") (pin "6") (pinfunction "6_6") (pintype "passive"))
      (node (ref "P4") (pin "7") (pinfunction "7_7") (pintype "passive"))
      (node (ref "P4") (pin "8") (pinfunction "8_8") (pintype "passive"))
      (node (ref "P5") (pin "3") (pinfunction "3_3") (pintype "passive"))
      (node (ref "P7") (pin "1") (pinfunction "1_1") (pintype "passive"))
      (node (ref "P8") (pin "1") (pinfunction "1_1") (pintype "passive"))
      (node (ref "P8") (pin "2") (pinfunction "2_2") (pintype "passive"))
      (node (ref "P8") (pin "3") (pinfunction "3_3") (pintype "passive"))
      (node (ref "P8") (pin "4") (pinfunction "4_4") (pintype "passive"))
      (node (ref "P8") (pin "5") (pinfunction "5_5") (pintype "passive"))
      (node (ref "P8") (pin "6") (pinfunction "6_6") (pintype "passive"))
      (node (ref "P8") (pin "7") (pinfunction "7_7") (pintype "passive"))
      (node (ref "P8") (pin "8") (pinfunction "8_8") (pintype "passive"))
      (node (ref "P9") (pin "4") (pinfunction "4_4") (pintype "passive"))
      (node (ref "Q1") (pin "1") (pinfunction "E_1") (pintype "passive"))
      (node (ref "R15") (pin "1") (pinfunction "1_1") (pintype "passive"))
      (node (ref "R16") (pin "1") (pinfunction "1_1") (pintype "passive"))
      (node (ref "R18") (pin "1") (pinfunction "1_1") (pintype "passive"))
      (node (ref "R19") (pin "1") (pinfunction "1_1") (pintype "passive"))
      (node (ref "R26") (pin "1") (pinfunction "1_1") (pintype "passive"))
      (node (ref "R5") (pin "1") (pinfunction "1_1") (pintype "passive"))
      (node (ref "R6") (pin "1") (pinfunction "1_1") (pintype "passive"))
      (node (ref "R8") (pin "1") (pinfunction "1_1") (pintype "passive"))
      (node (ref "R9") (pin "1") (pinfunction "1_1") (pintype "passive"))
      (node (ref "S1") (pin "1") (pinfunction "154_1") (pintype "passive"))
      (node (ref "S1") (pin "3") (pinfunction "155_3") (pintype "passive"))
      (node (ref "TJA1") (pin "3") (pinfunction "VCC_3") (pintype "passive"))
      (node (ref "TJA1") (pin "8") (pinfunction "RS_8") (pintype "passive"))
      (node (ref "U1") (pin "107") (pinfunction "VSS_107") (pintype "passive"))
      (node (ref "U1") (pin "120") (pinfunction "VSS_120") (pintype "passive"))
      (node (ref "U1") (pin "130") (pinfunction "VSS_130") (pintype "passive"))
      (node (ref "U1") (pin "143") (pinfunction "PDR_ON_143") (pintype "passive"))
      (node (ref "U1") (pin "16") (pinfunction "VSS_16") (pintype "passive"))
      (node (ref "U1") (pin "31") (pinfunction "VSSA_31") (pintype "passive"))
      (node (ref "U1") (pin "38") (pinfunction "VSS_38") (pintype "passive"))
      (node (ref "U1") (pin "51") (pinfunction "VSS_51") (pintype "passive"))
      (node (ref "U1") (pin "61") (pinfunction "VSS_61") (pintype "passive"))
      (node (ref "U1") (pin "83") (pinfunction "VSS_83") (pintype "passive"))
      (node (ref "U1") (pin "94") (pinfunction "VSS_94") (pintype "passive"))
      (node (ref "U2") (pin "1") (pinfunction "GND_1") (pintype "passive"))
    )
    (net (code "89") (name "Net-(LED1-Pad1)") (class "Default")
      (node (ref "LED1") (pin "1") (pinfunction "1_1") (pintype "passive"))
      (node (ref "R2") (pin "2") (pinfunction "2_2") (pintype "passive"))
    )
    (net (code "90") (name "Net-(LED2-Pad1)") (class "Default")
      (node (ref "LED2") (pin "1") (pinfunction "1_1") (pintype "passive"))
      (node (ref "R30") (pin "1") (pinfunction "1_1") (pintype "passive"))
    )
    (net (code "91") (name "Net-(LED3-Pad1)") (class "Default")
      (node (ref "LED3") (pin "1") (pinfunction "1_1") (pintype "passive"))
      (node (ref "R31") (pin "1") (pinfunction "1_1") (pintype "passive"))
    )
    (net (code "92") (name "Net-(LED4-Pad1)") (class "Default")
      (node (ref "LED4") (pin "1") (pinfunction "1_1") (pintype "passive"))
      (node (ref "R32") (pin "1") (pinfunction "1_1") (pintype "passive"))
    )
    (net (code "93") (name "Net-(LED5-Pad1)") (class "Default")
      (node (ref "LED5") (pin "1") (pinfunction "1_1") (pintype "passive"))
      (node (ref "R33") (pin "1") (pinfunction "1_1") (pintype "passive"))
    )
    (net (code "94") (name "Net-(LED6-Pad1)") (class "Default")
      (node (ref "LED6") (pin "1") (pinfunction "1_1") (pintype "passive"))
      (node (ref "R34") (pin "1") (pinfunction "1_1") (pintype "passive"))
    )
    (net (code "95") (name "Net-(LED7-Pad1)") (class "Default")
      (node (ref "LED7") (pin "1") (pinfunction "1_1") (pintype "passive"))
      (node (ref "R35") (pin "1") (pinfunction "1_1") (pintype "passive"))
    )
    (net (code "96") (name "Net-(LED8-Pad1)") (class "Default")
      (node (ref "LED8") (pin "1") (pinfunction "1_1") (pintype "passive"))
      (node (ref "R36") (pin "1") (pinfunction "1_1") (pintype "passive"))
    )
    (net (code "97") (name "Net-(LED9-Pad1)") (class "Default")
      (node (ref "LED9") (pin "1") (pinfunction "1_1") (pintype "passive"))
      (node (ref "R37") (pin "1") (pinfunction "1_1") (pintype "passive"))
    )
    (net (code "98") (name "Net-(LM1-1Non_Invert)") (class "Default")
      (node (ref "LM1") (pin "3") (pinfunction "1Non_Invert_3") (pintype "passive"))
      (node (ref "R6") (pin "2") (pinfunction "2_2") (pintype "passive"))
      (node (ref "R7") (pin "1") (pinfunction "1_1") (pintype "passive"))
    )
    (net (code "99") (name "Net-(LM1-2Non_Invert)") (class "Default")
      (node (ref "LM1") (pin "5") (pinfunction "2Non_Invert_5") (pintype "passive"))
      (node (ref "R12") (pin "1") (pinfunction "1_1") (pintype "passive"))
      (node (ref "R9") (pin "2") (pinfunction "2_2") (pintype "passive"))
    )
    (net (code "100") (name "Net-(LM1-3Non_Invert)") (class "Default")
      (node (ref "LM1") (pin "10") (pinfunction "3Non_Invert_10") (pintype "passive"))
      (node (ref "R13") (pin "1") (pinfunction "1_1") (pintype "passive"))
      (node (ref "R8") (pin "2") (pinfunction "2_2") (pintype "passive"))
    )
    (net (code "101") (name "Net-(LM1-4Non_Invert)") (class "Default")
      (node (ref "LM1") (pin "12") (pinfunction "4Non_Invert_12") (pintype "passive"))
      (node (ref "R4") (pin "2") (pinfunction "2_2") (pintype "passive"))
      (node (ref "R5") (pin "2") (pinfunction "2_2") (pintype "passive"))
    )
    (net (code "102") (name "Net-(LM2-1Non_Invert)") (class "Default")
      (node (ref "LM2") (pin "3") (pinfunction "1Non_Invert_3") (pintype "passive"))
      (node (ref "R16") (pin "2") (pinfunction "2_2") (pintype "passive"))
      (node (ref "R17") (pin "1") (pinfunction "1_1") (pintype "passive"))
    )
    (net (code "103") (name "Net-(LM2-2Non_Invert)") (class "Default")
      (node (ref "LM2") (pin "5") (pinfunction "2Non_Invert_5") (pintype "passive"))
      (node (ref "R19") (pin "2") (pinfunction "2_2") (pintype "passive"))
      (node (ref "R20") (pin "1") (pinfunction "1_1") (pintype "passive"))
    )
    (net (code "104") (name "Net-(LM2-3Non_Invert)") (class "Default")
      (node (ref "LM2") (pin "10") (pinfunction "3Non_Invert_10") (pintype "passive"))
      (node (ref "R18") (pin "2") (pinfunction "2_2") (pintype "passive"))
      (node (ref "R21") (pin "1") (pinfunction "1_1") (pintype "passive"))
    )
    (net (code "105") (name "Net-(LM2-4Non_Invert)") (class "Default")
      (node (ref "LM2") (pin "12") (pinfunction "4Non_Invert_12") (pintype "passive"))
      (node (ref "R14") (pin "2") (pinfunction "2_2") (pintype "passive"))
      (node (ref "R15") (pin "2") (pinfunction "2_2") (pintype "passive"))
    )
    (net (code "106") (name "Net-(Q1-B)") (class "Default")
      (node (ref "Q1") (pin "2") (pinfunction "B_2") (pintype "passive"))
      (node (ref "R25") (pin "2") (pinfunction "2_2") (pintype "passive"))
      (node (ref "R26") (pin "2") (pinfunction "2_2") (pintype "passive"))
    )
    (net (code "107") (name "Net-(Q1-C)") (class "Default")
      (node (ref "Buzzer1") (pin "2") (pinfunction "2_2") (pintype "passive"))
      (node (ref "D1") (pin "2") (pinfunction "2_2") (pintype "passive"))
      (node (ref "Q1") (pin "3") (pinfunction "C_3") (pintype "passive"))
    )
    (net (code "108") (name "Net-(RGB1-B)") (class "Default")
      (node (ref "R28") (pin "1") (pinfunction "1_1") (pintype "passive"))
      (node (ref "RGB1") (pin "2") (pinfunction "B_2") (pintype "passive"))
    )
    (net (code "109") (name "Net-(RGB1-G)") (class "Default")
      (node (ref "R27") (pin "2") (pinfunction "2_2") (pintype "passive"))
      (node (ref "RGB1") (pin "4") (pinfunction "G_4") (pintype "passive"))
    )
    (net (code "110") (name "Net-(RGB1-R)") (class "Default")
      (node (ref "R29") (pin "2") (pinfunction "2_2") (pintype "passive"))
      (node (ref "RGB1") (pin "3") (pinfunction "R_3") (pintype "passive"))
    )
    (net (code "111") (name "Net-(TJA1-CANH)") (class "Default")
      (node (ref "R22") (pin "1") (pinfunction "1_1") (pintype "passive"))
      (node (ref "TJA1") (pin "7") (pinfunction "CANH_7") (pintype "passive"))
    )
    (net (code "112") (name "Net-(TJA1-CANL)") (class "Default")
      (node (ref "R23") (pin "1") (pinfunction "1_1") (pintype "passive"))
      (node (ref "TJA1") (pin "6") (pinfunction "CANL_6") (pintype "passive"))
    )
    (net (code "113") (name "Net-(U1-VCAP_1)") (class "Default")
      (node (ref "C16") (pin "2") (pinfunction "2_2") (pintype "passive"))
      (node (ref "U1") (pin "71") (pinfunction "VCAP_1_71") (pintype "passive"))
    )
    (net (code "114") (name "Net-(U1-VCAP_2)") (class "Default")
      (node (ref "C15") (pin "2") (pinfunction "2_2") (pintype "passive"))
      (node (ref "U1") (pin "106") (pinfunction "VCAP_2_106") (pintype "passive"))
    )
    (net (code "115") (name "Net-(U2-VIN)") (class "Default")
      (node (ref "C4") (pin "1") (pinfunction "1_1") (pintype "passive"))
      (node (ref "C5") (pin "1") (pinfunction "1_1") (pintype "passive"))
      (node (ref "F1") (pin "1") (pinfunction "1_1") (pintype "passive"))
      (node (ref "R2") (pin "1") (pinfunction "1_1") (pintype "passive"))
      (node (ref "U2") (pin "3") (pinfunction "VIN_3") (pintype "passive"))
    )
    (net (code "116") (name "VCC") (class "Default")
      (node (ref "Buzzer1") (pin "1") (pinfunction "1_1") (pintype "passive"))
      (node (ref "C12") (pin "2") (pinfunction "2_2") (pintype "passive"))
      (node (ref "C17") (pin "2") (pinfunction "2_2") (pintype "passive"))
      (node (ref "C18") (pin "2") (pinfunction "2_2") (pintype "passive"))
      (node (ref "C19") (pin "2") (pinfunction "2_2") (pintype "passive"))
      (node (ref "C20") (pin "2") (pinfunction "2_2") (pintype "passive"))
      (node (ref "C21") (pin "2") (pinfunction "2_2") (pintype "passive"))
      (node (ref "C22") (pin "2") (pinfunction "2_2") (pintype "passive"))
      (node (ref "C23") (pin "2") (pinfunction "2_2") (pintype "passive"))
      (node (ref "C24") (pin "2") (pinfunction "2_2") (pintype "passive"))
      (node (ref "C25") (pin "2") (pinfunction "2_2") (pintype "passive"))
      (node (ref "C26") (pin "2") (pinfunction "2_2") (pintype "passive"))
      (node (ref "C27") (pin "2") (pinfunction "2_2") (pintype "passive"))
      (node (ref "C28") (pin "2") (pinfunction "2_2") (pintype "passive"))
      (node (ref "C29") (pin "2") (pinfunction "2_2") (pintype "passive"))
      (node (ref "C3") (pin "1") (pinfunction "1_1") (pintype "passive"))
      (node (ref "C7") (pin "2") (pinfunction "2_2") (pintype "passive"))
      (node (ref "C8") (pin "2") (pinfunction "2_2") (pintype "passive"))
      (node (ref "C9") (pin "1") (pinfunction "1_1") (pintype "passive"))
      (node (ref "D1") (pin "1") (pinfunction "1_1") (pintype "passive"))
      (node (ref "E1") (pin "1") (pinfunction "A_1") (pintype "passive"))
      (node (ref "LM1") (pin "4") (pinfunction "VCC+_4") (pintype "passive"))
      (node (ref "LM2") (pin "4") (pinfunction "VCC+_4") (pintype "passive"))
      (node (ref "P10") (pin "1") (pinfunction "1_1") (pintype "passive"))
      (node (ref "P11") (pin "1") (pinfunction "1_1") (pintype "passive"))
      (node (ref "P12") (pin "1") (pinfunction "1_1") (pintype "passive"))
      (node (ref "P13") (pin "1") (pinfunction "1_1") (pintype "passive"))
      (node (ref "P14") (pin "1") (pinfunction "1_1") (pintype "passive"))
      (node (ref "P16") (pin "1") (pinfunction "1_1") (pintype "passive"))
      (node (ref "P17") (pin "2") (pinfunction "2_2") (pintype "passive"))
      (node (ref "P18") (pin "1") (pinfunction "1_1") (pintype "passive"))
      (node (ref "P3") (pin "1") (pinfunction "1_1") (pintype "passive"))
      (node (ref "P3") (pin "2") (pinfunction "2_2") (pintype "passive"))
      (node (ref "P3") (pin "3") (pinfunction "3_3") (pintype "passive"))
      (node (ref "P3") (pin "4") (pinfunction "4_4") (pintype "passive"))
      (node (ref "P3") (pin "5") (pinfunction "5_5") (pintype "passive"))
      (node (ref "P3") (pin "6") (pinfunction "6_6") (pintype "passive"))
      (node (ref "P3") (pin "7") (pinfunction "7_7") (pintype "passive"))
      (node (ref "P3") (pin "8") (pinfunction "8_8") (pintype "passive"))
      (node (ref "P5") (pin "4") (pinfunction "4_4") (pintype "passive"))
      (node (ref "P7") (pin "2") (pinfunction "2_2") (pintype "passive"))
      (node (ref "P9") (pin "1") (pinfunction "1_1") (pintype "passive"))
      (node (ref "R10") (pin "2") (pinfunction "2_2") (pintype "passive"))
      (node (ref "R11") (pin "1") (pinfunction "1_1") (pintype "passive"))
      (node (ref "R3") (pin "2") (pinfunction "2_2") (pintype "passive"))
      (node (ref "R38") (pin "1") (pinfunction "1_1") (pintype "passive"))
      (node (ref "RGB1") (pin "1") (pinfunction "V_1") (pintype "passive"))
      (node (ref "TJA1") (pin "2") (pinfunction "GND_2") (pintype "passive"))
      (node (ref "U1") (pin "108") (pinfunction "VDD_108") (pintype "passive"))
      (node (ref "U1") (pin "121") (pinfunction "VDD_121") (pintype "passive"))
      (node (ref "U1") (pin "131") (pinfunction "VDD_131") (pintype "passive"))
      (node (ref "U1") (pin "144") (pinfunction "VDD_144") (pintype "passive"))
      (node (ref "U1") (pin "17") (pinfunction "VDD_17") (pintype "passive"))
      (node (ref "U1") (pin "30") (pinfunction "VDD_30") (pintype "passive"))
      (node (ref "U1") (pin "39") (pinfunction "VDD_39") (pintype "passive"))
      (node (ref "U1") (pin "52") (pinfunction "VDD_52") (pintype "passive"))
      (node (ref "U1") (pin "62") (pinfunction "VDD_62") (pintype "passive"))
      (node (ref "U1") (pin "72") (pinfunction "VDD_72") (pintype "passive"))
      (node (ref "U1") (pin "84") (pinfunction "VDD_84") (pintype "passive"))
      (node (ref "U1") (pin "95") (pinfunction "VDD_95") (pintype "passive"))
      (node (ref "U2") (pin "2") (pinfunction "VOUT_2") (pintype "passive"))
    )
    (net (code "117") (name "VCC_IN") (class "Default")
      (node (ref "F1") (pin "2") (pinfunction "2_2") (pintype "passive"))
      (node (ref "P1") (pin "1") (pinfunction "1_1") (pintype "passive"))
    )
    (net (code "118") (name "unconnected-(TJA1-VREF-Pad5)") (class "Default")
      (node (ref "TJA1") (pin "5") (pinfunction "VREF_5") (pintype "passive"))
    )
    (net (code "119") (name "unconnected-(U1-FSMC_A6{slash}PF12-Pad50)") (class "Default")
      (node (ref "U1") (pin "50") (pinfunction "FSMC_A6/PF12_50") (pintype "passive"))
    )
    (net (code "120") (name "unconnected-(U1-FSMC_A7{slash}PF13-Pad53)") (class "Default")
      (node (ref "U1") (pin "53") (pinfunction "FSMC_A7/PF13_53") (pintype "passive"))
    )
    (net (code "121") (name "unconnected-(U1-FSMC_A8{slash}PF14-Pad54)") (class "Default")
      (node (ref "U1") (pin "54") (pinfunction "FSMC_A8/PF14_54") (pintype "passive"))
    )
    (net (code "122") (name "unconnected-(U1-FSMC_A9{slash}PF15-Pad55)") (class "Default")
      (node (ref "U1") (pin "55") (pinfunction "FSMC_A9/PF15_55") (pintype "passive"))
    )
    (net (code "123") (name "unconnected-(U1-FSMC_A10{slash}PG0-Pad56)") (class "Default")
      (node (ref "U1") (pin "56") (pinfunction "FSMC_A10/PG0_56") (pintype "passive"))
    )
    (net (code "124") (name "unconnected-(U1-FSMC_A11{slash}PG1-Pad57)") (class "Default")
      (node (ref "U1") (pin "57") (pinfunction "FSMC_A11/PG1_57") (pintype "passive"))
    )
    (net (code "125") (name "unconnected-(U1-FSMC_A12{slash}PG2-Pad87)") (class "Default")
      (node (ref "U1") (pin "87") (pinfunction "FSMC_A12/PG2_87") (pintype "passive"))
    )
    (net (code "126") (name "unconnected-(U1-FSMC_A13{slash}PG3-Pad88)") (class "Default")
      (node (ref "U1") (pin "88") (pinfunction "FSMC_A13/PG3_88") (pintype "passive"))
    )
    (net (code "127") (name "unconnected-(U1-FSMC_A22{slash}PE6-Pad5)") (class "Default")
      (node (ref "U1") (pin "5") (pinfunction "FSMC_A22/PE6_5") (pintype "passive"))
    )
    (net (code "128") (name "unconnected-(U1-FSMC_D12{slash}PE15-Pad68)") (class "Default")
      (node (ref "U1") (pin "68") (pinfunction "FSMC_D12/PE15_68") (pintype "passive"))
    )
    (net (code "129") (name "unconnected-(U1-FSMC_NBL0{slash}PE0-Pad141)") (class "Default")
      (node (ref "U1") (pin "141") (pinfunction "FSMC_NBL0/PE0_141") (pintype "passive"))
    )
    (net (code "130") (name "unconnected-(U1-FSMC_NBL1{slash}PE1-Pad142)") (class "Default")
      (node (ref "U1") (pin "142") (pinfunction "FSMC_NBL1/PE1_142") (pintype "passive"))
    )
    (net (code "131") (name "unconnected-(U1-FSMC_NCE4_1{slash}FSMC_NE3{slash}PG10-Pad125)") (class "Default")
      (node (ref "U1") (pin "125") (pinfunction "FSMC_NCE4_1/FSMC_NE3/PG10_125") (pintype "passive"))
    )
    (net (code "132") (name "unconnected-(U1-FSMC_NCE4_2{slash}PG11-Pad126)") (class "Default")
      (node (ref "U1") (pin "126") (pinfunction "FSMC_NCE4_2/PG11_126") (pintype "passive"))
    )
    (net (code "133") (name "unconnected-(U1-I2C2_SMBA{slash}FSMC_A2{slash}PF2-Pad12)") (class "Default")
      (node (ref "U1") (pin "12") (pinfunction "I2C2_SMBA/FSMC_A2/PF2_12") (pintype "passive"))
    )
    (net (code "134") (name "unconnected-(U1-PA3{slash}USART2_RX-Pad37)") (class "Default")
      (node (ref "U1") (pin "37") (pinfunction "PA3/USART2_RX_37") (pintype "passive"))
    )
    (net (code "135") (name "unconnected-(U1-PA8{slash}USART1_CK-Pad100)") (class "Default")
      (node (ref "U1") (pin "100") (pinfunction "PA8/USART1_CK_100") (pintype "passive"))
    )
    (net (code "136") (name "unconnected-(U1-PA15{slash}SPI3_NSS{slash}I2S3_WS-Pad110)") (class "Default")
      (node (ref "U1") (pin "110") (pinfunction "PA15/SPI3_NSS/I2S3_WS_110") (pintype "passive"))
    )
    (net (code "137") (name "unconnected-(U1-PB4{slash}SPI3_MISO{slash}SPI1_MISO{slash}I2S3ext_SD-Pad134)") (class "Default")
      (node (ref "U1") (pin "134") (pinfunction "PB4/SPI3_MISO/SPI1_MISO/I2S3ext_SD_134") (pintype "passive"))
    )
    (net (code "138") (name "unconnected-(U1-PB9{slash}SPI2_NSS{slash}I2S2_WS{slash}I2C1_SDA{slash}CAN1_TX-Pad140)") (class "Default")
      (node (ref "U1") (pin "140") (pinfunction "PB9/SPI2_NSS/I2S2_WS/I2C1_SDA/CAN1_TX_140") (pintype "passive"))
    )
    (net (code "139") (name "unconnected-(U1-PC0-Pad26)") (class "Default")
      (node (ref "U1") (pin "26") (pinfunction "PC0_26") (pintype "passive"))
    )
    (net (code "140") (name "unconnected-(U1-PC1-Pad27)") (class "Default")
      (node (ref "U1") (pin "27") (pinfunction "PC1_27") (pintype "passive"))
    )
    (net (code "141") (name "unconnected-(U1-PC2{slash}SPI2_MISO{slash}I2S2ext_SD-Pad28)") (class "Default")
      (node (ref "U1") (pin "28") (pinfunction "PC2/SPI2_MISO/I2S2ext_SD_28") (pintype "passive"))
    )
    (net (code "142") (name "unconnected-(U1-PC3{slash}SPI2_MOSI{slash}I2S2_SD-Pad29)") (class "Default")
      (node (ref "U1") (pin "29") (pinfunction "PC3/SPI2_MOSI/I2S2_SD_29") (pintype "passive"))
    )
    (net (code "143") (name "unconnected-(U1-PC4-Pad44)") (class "Default")
      (node (ref "U1") (pin "44") (pinfunction "PC4_44") (pintype "passive"))
    )
    (net (code "144") (name "unconnected-(U1-PC5-Pad45)") (class "Default")
      (node (ref "U1") (pin "45") (pinfunction "PC5_45") (pintype "passive"))
    )
    (net (code "145") (name "unconnected-(U1-PC13-Pad7)") (class "Default")
      (node (ref "U1") (pin "7") (pinfunction "PC13_7") (pintype "passive"))
    )
    (net (code "146") (name "unconnected-(U1-PC14{slash}OSC32_IN-Pad8)") (class "Default")
      (node (ref "U1") (pin "8") (pinfunction "PC14/OSC32_IN_8") (pintype "passive"))
    )
    (net (code "147") (name "unconnected-(U1-PC15{slash}OSC32_OUT-Pad9)") (class "Default")
      (node (ref "U1") (pin "9") (pinfunction "PC15/OSC32_OUT_9") (pintype "passive"))
    )
    (net (code "148") (name "unconnected-(U1-PD0{slash}FSMC_D2{slash}CAN1_RX-Pad114)") (class "Default")
      (node (ref "U1") (pin "114") (pinfunction "PD0/FSMC_D2/CAN1_RX_114") (pintype "passive"))
    )
    (net (code "149") (name "unconnected-(U1-PD1{slash}FSMC_D2{slash}CAN1_TX-Pad115)") (class "Default")
      (node (ref "U1") (pin "115") (pinfunction "PD1/FSMC_D2/CAN1_TX_115") (pintype "passive"))
    )
    (net (code "150") (name "unconnected-(U1-PD3{slash}FSMC_CLK{slash}USART2_CTS-Pad117)") (class "Default")
      (node (ref "U1") (pin "117") (pinfunction "PD3/FSMC_CLK/USART2_CTS_117") (pintype "passive"))
    )
    (net (code "151") (name "unconnected-(U1-PD4{slash}FSMC_NOE{slash}USART2_RTS-Pad118)") (class "Default")
      (node (ref "U1") (pin "118") (pinfunction "PD4/FSMC_NOE/USART2_RTS_118") (pintype "passive"))
    )
    (net (code "152") (name "unconnected-(U1-PD7{slash}FSMC_NE1{slash}FSMC_NCE2{slash}USART2_CK-Pad123)") (class "Default")
      (node (ref "U1") (pin "123") (pinfunction "PD7/FSMC_NE1/FSMC_NCE2/USART2_CK_123") (pintype "passive"))
    )
    (net (code "153") (name "unconnected-(U1-PD10{slash}FSMC_D15{slash}USART3_CK-Pad79)") (class "Default")
      (node (ref "U1") (pin "79") (pinfunction "PD10/FSMC_D15/USART3_CK_79") (pintype "passive"))
    )
    (net (code "154") (name "unconnected-(U1-PD11{slash}FSMC_CLE{slash}FSMC_A16{slash}USART3_CTS-Pad80)") (class "Default")
      (node (ref "U1") (pin "80") (pinfunction "PD11/FSMC_CLE/FSMC_A16/USART3_CTS_80") (pintype "passive"))
    )
    (net (code "155") (name "unconnected-(U1-PF11-Pad49)") (class "Default")
      (node (ref "U1") (pin "49") (pinfunction "PF11_49") (pintype "passive"))
    )
    (net (code "156") (name "unconnected-(U1-USART6_RTS{slash}FSMC_NE4{slash}PG12-Pad127)") (class "Default")
      (node (ref "U1") (pin "127") (pinfunction "USART6_RTS/FSMC_NE4/PG12_127") (pintype "passive"))
    )
    (net (code "157") (name "unconnected-(U1-USART6_RTS{slash}PG8-Pad93)") (class "Default")
      (node (ref "U1") (pin "93") (pinfunction "USART6_RTS/PG8_93") (pintype "passive"))
    )
    (net (code "158") (name "unconnected-(U1-USART6_RX{slash}FSMC_NE2{slash}FSMC_NCE3{slash}PG9-Pad124)") (class "Default")
      (node (ref "U1") (pin "124") (pinfunction "USART6_RX/FSMC_NE2/FSMC_NCE3/PG9_124") (pintype "passive"))
    )
    (net (code "159") (name "unconnected-(U1-VBAT-Pad6)") (class "Default")
      (node (ref "U1") (pin "6") (pinfunction "VBAT_6") (pintype "passive"))
    )
  )
)
